# GRBLduino_Uno_Rev3-02-TH.net
KiCad netlist of a schematic drawn in EAGLE
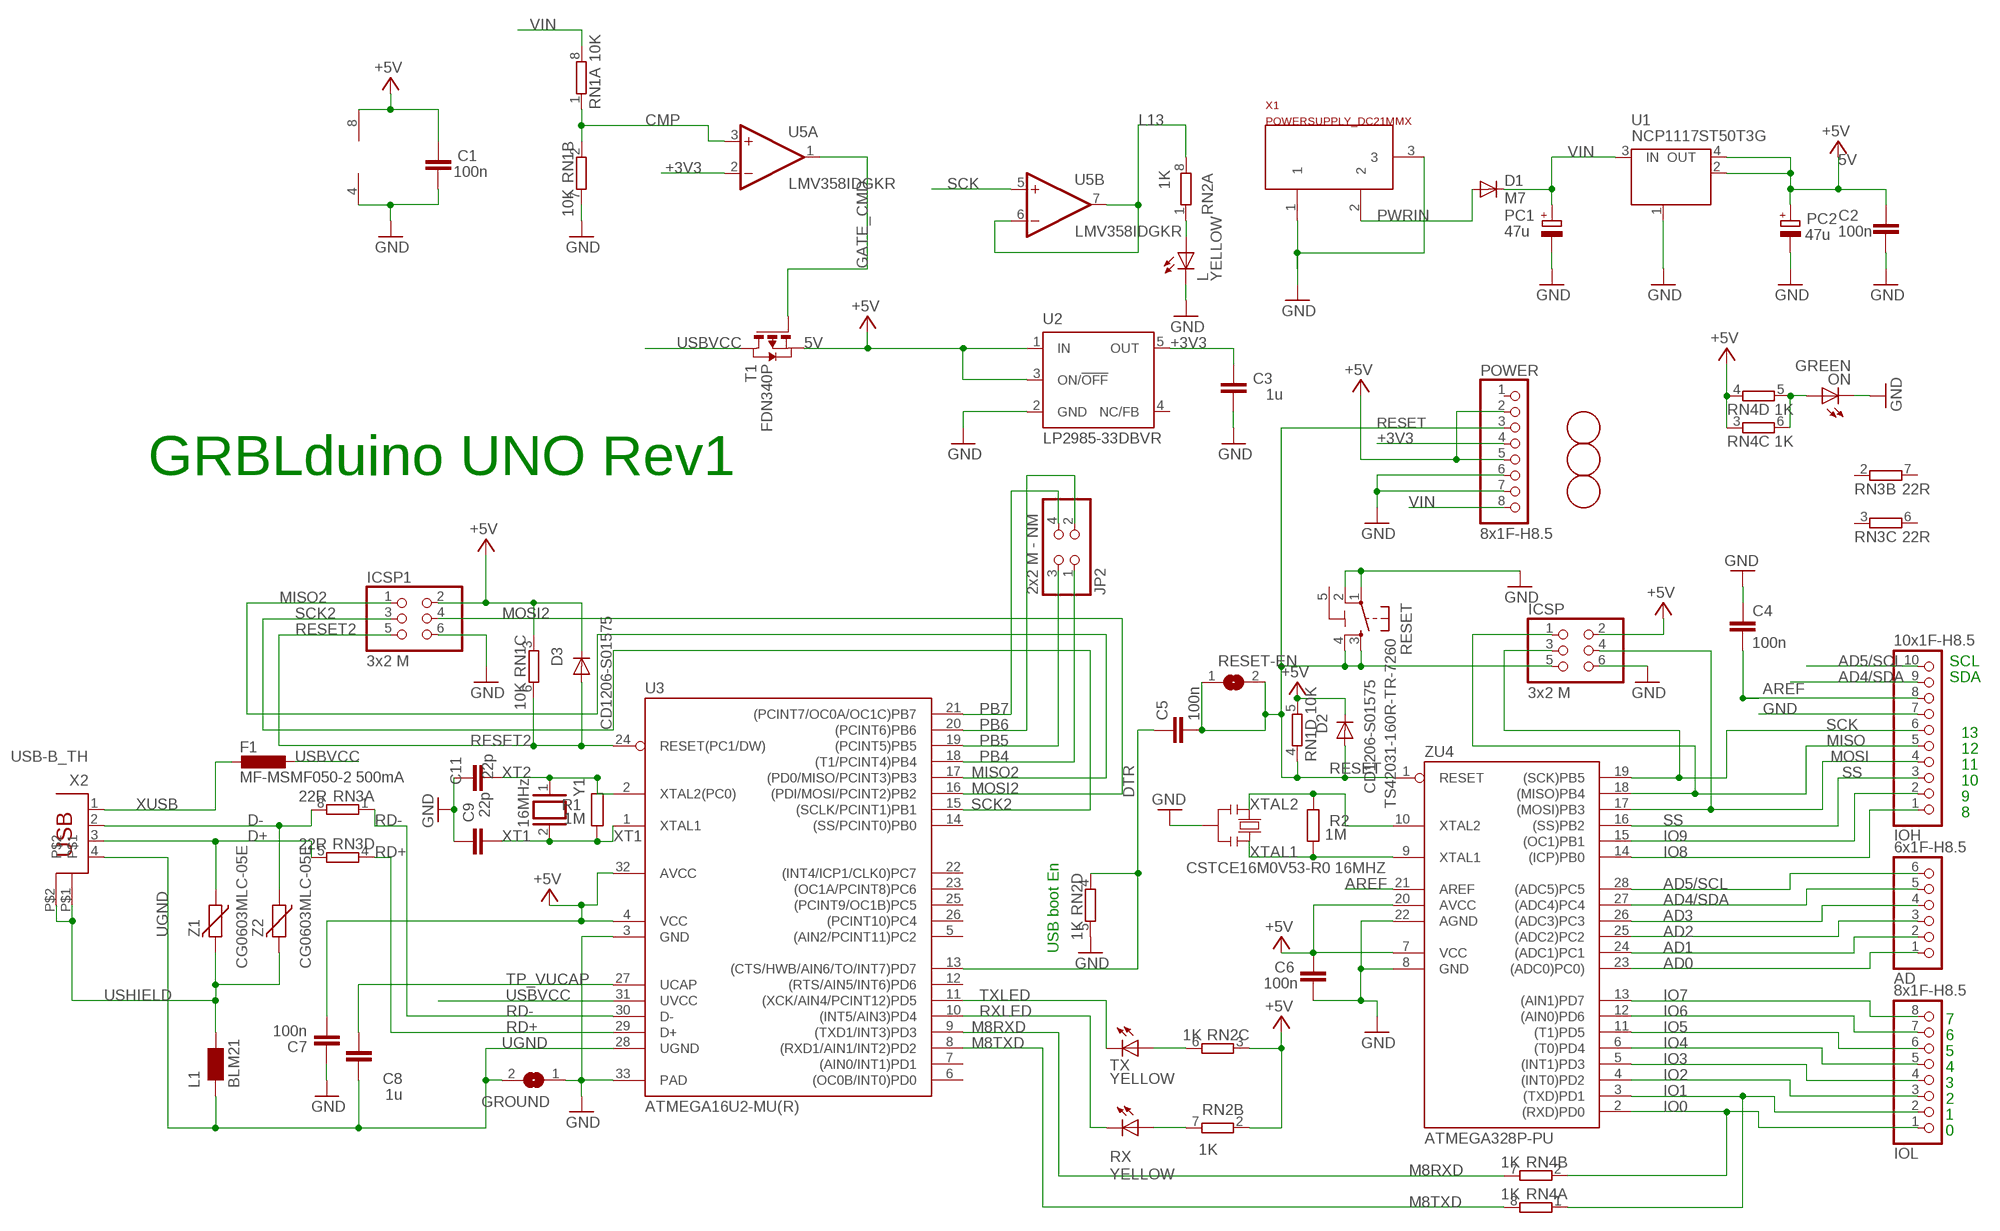
[diagram p0: schematic, sheet 1]
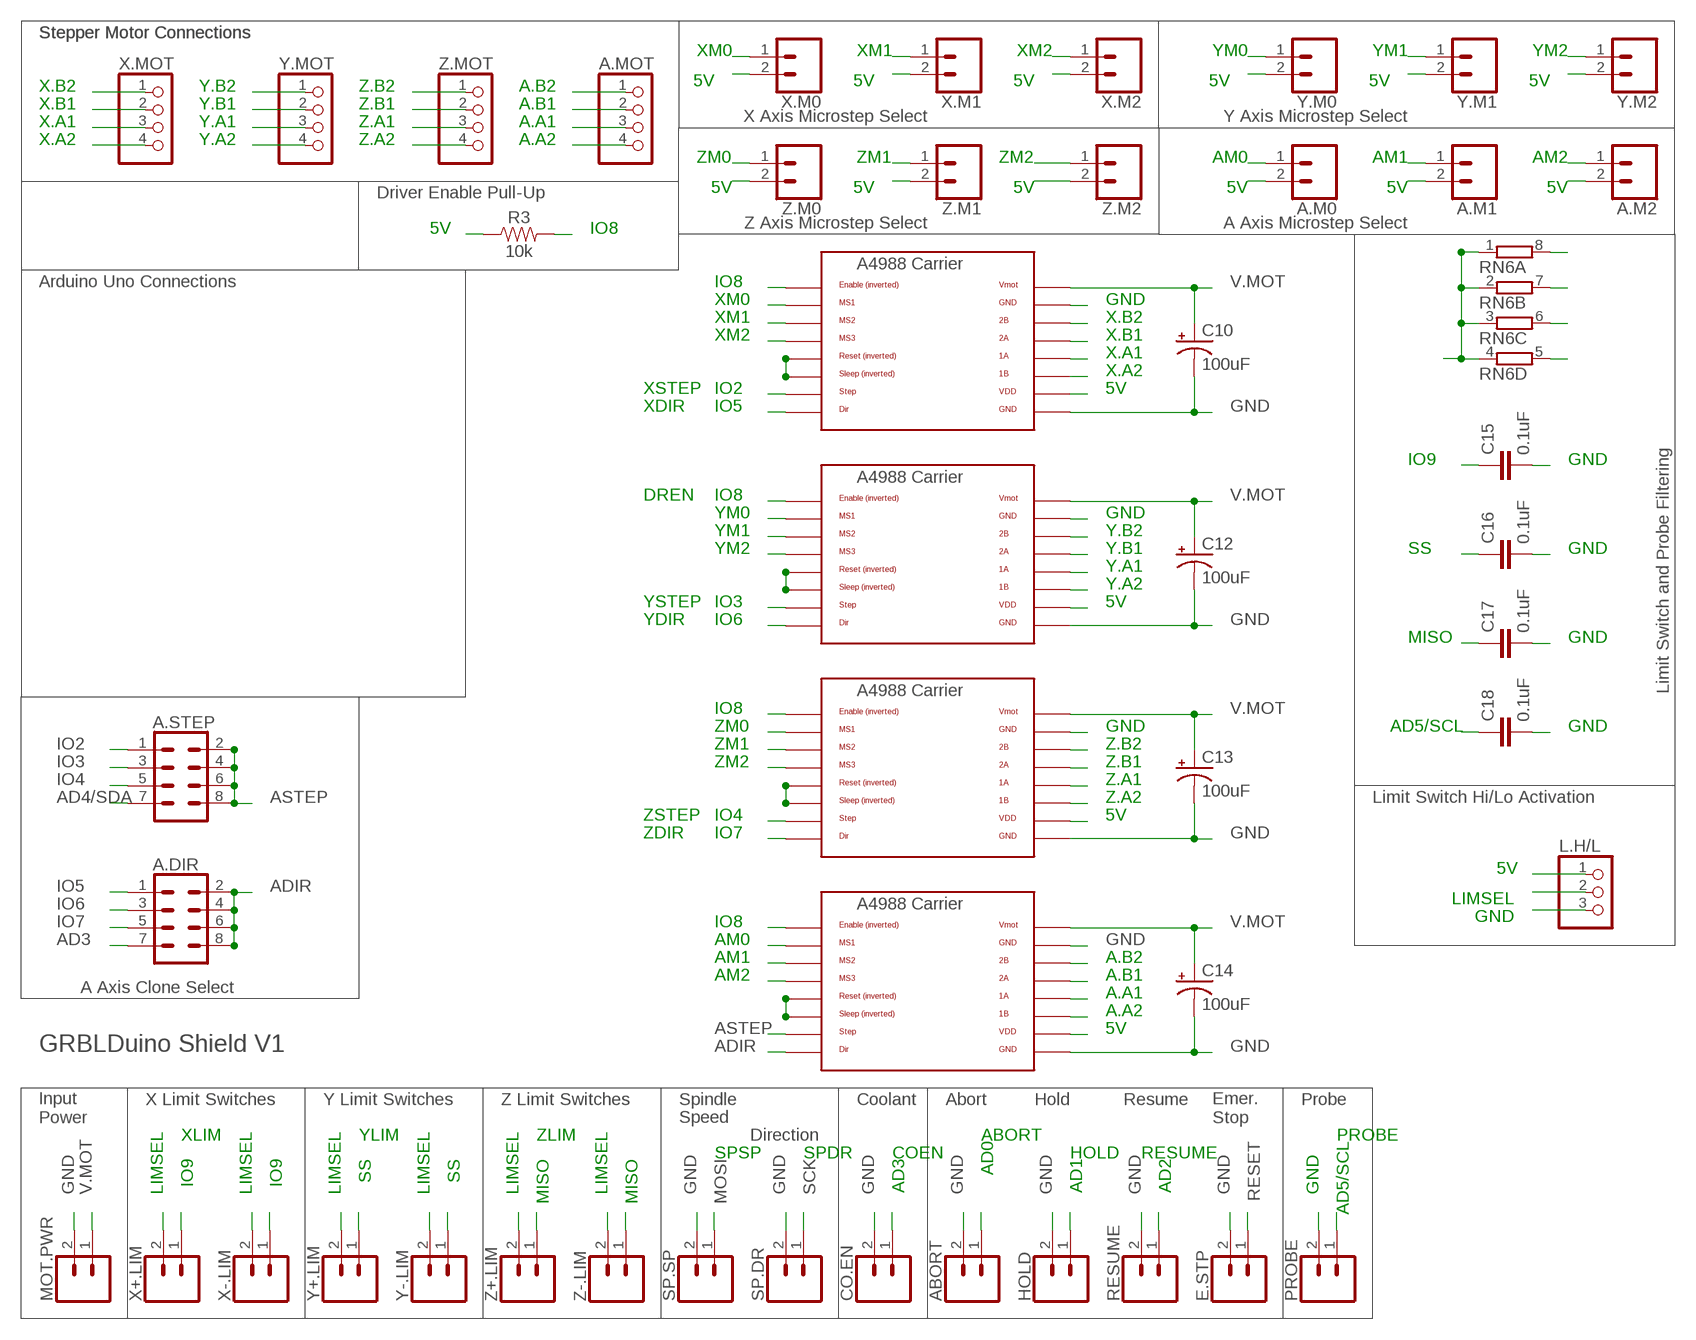
[diagram p1: schematic, sheet 2]

(export (version "E")
  (design (tool "Eeschema 10.0.6"))
  (components
    (comp (ref "AD")
      (value "6x1F-H8.5")
      (footprint "eagle-import:1X06")
      (libsource (lib "eagle-import") (part "PINHD-1X6"))
    )
    (comp (ref "C1")
      (value "100n")
      (footprint "eagle-import:C0603-ROUND")
      (libsource (lib "eagle-import") (part "C-EU0603-RND"))
    )
    (comp (ref "C2")
      (value "100n")
      (footprint "eagle-import:C0603-ROUND")
      (libsource (lib "eagle-import") (part "C-EU0603-RND"))
    )
    (comp (ref "C3")
      (value "1u")
      (footprint "eagle-import:C0603-ROUND")
      (libsource (lib "eagle-import") (part "C-EU0603-RND"))
    )
    (comp (ref "C4")
      (value "100n")
      (footprint "eagle-import:C0603-ROUND")
      (libsource (lib "eagle-import") (part "C-EU0603-RND"))
    )
    (comp (ref "C5")
      (value "100n")
      (footprint "eagle-import:C0603-ROUND")
      (libsource (lib "eagle-import") (part "C-EU0603-RND"))
    )
    (comp (ref "C6")
      (value "100n")
      (footprint "eagle-import:C0603-ROUND")
      (libsource (lib "eagle-import") (part "C-EU0603-RND"))
    )
    (comp (ref "C7")
      (value "100n")
      (footprint "eagle-import:C0603-ROUND")
      (libsource (lib "eagle-import") (part "C-EU0603-RND"))
    )
    (comp (ref "C8")
      (value "1u")
      (footprint "eagle-import:C0603-ROUND")
      (libsource (lib "eagle-import") (part "C-EU0603-RND"))
    )
    (comp (ref "C9")
      (value "22p")
      (footprint "eagle-import:C0603-ROUND")
      (libsource (lib "eagle-import") (part "C-EU0603-RND"))
    )
    (comp (ref "C11")
      (value "22p")
      (footprint "eagle-import:C0603-ROUND")
      (libsource (lib "eagle-import") (part "C-EU0603-RND"))
    )
    (comp (ref "D1")
      (value "M7")
      (footprint "eagle-import:SMB")
      (libsource (lib "eagle-import") (part "DIODE-SMB"))
    )
    (comp (ref "D2")
      (value "CD1206-S01575")
      (footprint "eagle-import:MINIMELF")
      (libsource (lib "eagle-import") (part "DIODE-MINIMELF"))
    )
    (comp (ref "D3")
      (value "CD1206-S01575")
      (footprint "eagle-import:MINIMELF")
      (libsource (lib "eagle-import") (part "DIODE-MINIMELF"))
    )
    (comp (ref "F1")
      (value "MF-MSMF050-2 500mA")
      (footprint "eagle-import:L1812")
      (libsource (lib "eagle-import") (part "L-EUL1812"))
    )
    (comp (ref "FD1")
      (value "FIDUCIALMOUNT")
      (footprint "eagle-import:FIDUCIA-MOUNT")
      (libsource (lib "eagle-import") (part "FIDUCIALMOUNT"))
    )
    (comp (ref "FD2")
      (value "FIDUCIALMOUNT")
      (footprint "eagle-import:FIDUCIA-MOUNT")
      (libsource (lib "eagle-import") (part "FIDUCIALMOUNT"))
    )
    (comp (ref "FD3")
      (value "FIDUCIALMOUNT")
      (footprint "eagle-import:FIDUCIA-MOUNT")
      (libsource (lib "eagle-import") (part "FIDUCIALMOUNT"))
    )
    (comp (ref "GROUND")
      (value "SJ")
      (footprint "eagle-import:SJ")
      (libsource (lib "eagle-import") (part "SJ"))
    )
    (comp (ref "ICSP")
      (value "3x2 M")
      (footprint "eagle-import:2X03")
      (libsource (lib "eagle-import") (part "PINHD-2X3"))
    )
    (comp (ref "ICSP1")
      (value "3x2 M")
      (footprint "eagle-import:2X03")
      (libsource (lib "eagle-import") (part "PINHD-2X3"))
    )
    (comp (ref "IOH")
      (value "10x1F-H8.5")
      (footprint "eagle-import:1X10")
      (libsource (lib "eagle-import") (part "PINHD-1X10_ARD"))
    )
    (comp (ref "IOL")
      (value "8x1F-H8.5")
      (footprint "eagle-import:1X08")
      (libsource (lib "eagle-import") (part "PINHD-1X8"))
    )
    (comp (ref "JP2")
      (value "2x2 M - NM")
      (footprint "eagle-import:2X02")
      (libsource (lib "eagle-import") (part "PINHD-2X2"))
    )
    (comp (ref "L")
      (value "YELLOW")
      (footprint "eagle-import:CHIP-LED0805")
      (libsource (lib "eagle-import") (part "LEDCHIP-LED0805"))
    )
    (comp (ref "L1")
      (value "BLM21")
      (footprint "eagle-import:0805")
      (libsource (lib "eagle-import") (part "WE-CBF_0805"))
    )
    (comp (ref "ON")
      (value "GREEN")
      (footprint "eagle-import:CHIP-LED0805")
      (libsource (lib "eagle-import") (part "LEDCHIP-LED0805"))
    )
    (comp (ref "PC1")
      (value "47u")
      (footprint "eagle-import:PANASONIC_D")
      (libsource (lib "eagle-import") (part "CPOL-EUD"))
    )
    (comp (ref "PC2")
      (value "47u")
      (footprint "eagle-import:PANASONIC_D")
      (libsource (lib "eagle-import") (part "CPOL-EUD"))
    )
    (comp (ref "POWER")
      (value "8x1F-H8.5")
      (footprint "eagle-import:1X08")
      (libsource (lib "eagle-import") (part "PINHD-1X8"))
    )
    (comp (ref "R1")
      (value "1M")
      (footprint "eagle-import:R0603-ROUND")
      (libsource (lib "eagle-import") (part "R-EU_R0603"))
    )
    (comp (ref "R2")
      (value "1M")
      (footprint "eagle-import:R0603-ROUND")
      (libsource (lib "eagle-import") (part "R-EU_R0603"))
    )
    (comp (ref "RESET")
      (value "TS42031-160R-TR-7260")
      (footprint "eagle-import:TS42")
      (libsource (lib "eagle-import") (part "TS42"))
    )
    (comp (ref "RESET-EN")
      (value "SJ")
      (footprint "eagle-import:SJ")
      (libsource (lib "eagle-import") (part "SJ"))
    )
    (comp (ref "RN1")
      (value "10K")
      (footprint "eagle-import:CAY16")
      (libsource (lib "eagle-import") (part "4R-NCAY16"))
    )
    (comp (ref "RN2")
      (value "1K")
      (footprint "eagle-import:CAY16")
      (libsource (lib "eagle-import") (part "4R-NCAY16"))
    )
    (comp (ref "RN3")
      (value "22R")
      (footprint "eagle-import:CAY16")
      (libsource (lib "eagle-import") (part "4R-NCAY16"))
    )
    (comp (ref "RN4")
      (value "1K")
      (footprint "eagle-import:CAY16")
      (libsource (lib "eagle-import") (part "4R-NCAY16"))
    )
    (comp (ref "RX")
      (value "YELLOW")
      (footprint "eagle-import:CHIP-LED0805")
      (libsource (lib "eagle-import") (part "LEDCHIP-LED0805"))
    )
    (comp (ref "T1")
      (value "FDN340P")
      (footprint "eagle-import:SOT-23")
      (libsource (lib "eagle-import") (part "PMOSSOT23"))
    )
    (comp (ref "TX")
      (value "YELLOW")
      (footprint "eagle-import:CHIP-LED0805")
      (libsource (lib "eagle-import") (part "LEDCHIP-LED0805"))
    )
    (comp (ref "U1")
      (value "NCP1117ST50T3G")
      (footprint "eagle-import:SOT223")
      (libsource (lib "eagle-import") (part "MC33269ST-3.3T3"))
    )
    (comp (ref "U2")
      (value "LP2985-33DBVR")
      (footprint "eagle-import:SOT23-DBV")
      (libsource (lib "eagle-import") (part "LP2985-XXDBVR33"))
    )
    (comp (ref "U3")
      (value "ATMEGA16U2-MU(R)")
      (footprint "eagle-import:MLF32")
      (libsource (lib "eagle-import") (part "ATMEGA16U2-MU"))
    )
    (comp (ref "U5")
      (value "LMV358IDGKR")
      (footprint "eagle-import:MSOP08")
      (libsource (lib "eagle-import") (part "LMV358?MMX"))
    )
    (comp (ref "X1")
      (value "POWERSUPPLY_DC21MMX")
      (footprint "eagle-import:POWERSUPPLY_DC-21MM")
      (libsource (lib "eagle-import") (part "POWERSUPPLY_DC21MMX"))
    )
    (comp (ref "X2")
      (value "USB-B_TH")
      (footprint "eagle-import:PN61729")
      (libsource (lib "eagle-import") (part "PN61729"))
    )
    (comp (ref "Y1")
      (value "16MHz")
      (footprint "eagle-import:QS")
      (libsource (lib "eagle-import") (part "XTAL/S"))
    )
    (comp (ref "Y2")
      (value "CSTCE16M0V53-R0 16MHZ")
      (footprint "eagle-import:RESONATOR")
      (libsource (lib "eagle-import") (part "RESONATORMU"))
    )
    (comp (ref "Z1")
      (value "CG0603MLC-05E")
      (footprint "eagle-import:CT_CN0603")
      (libsource (lib "eagle-import") (part "VARISTORCN0603"))
    )
    (comp (ref "Z2")
      (value "CG0603MLC-05E")
      (footprint "eagle-import:CT_CN0603")
      (libsource (lib "eagle-import") (part "VARISTORCN0603"))
    )
    (comp (ref "ZU4")
      (value "ATMEGA328P-PU")
      (footprint "eagle-import:DIL28-3")
      (libsource (lib "eagle-import") (part "ATMEGA328P-PU"))
    )
    (comp (ref "A.DIR")
      (value "CONN_04X2")
      (footprint "eagle-import:2X4")
      (libsource (lib "eagle-import") (part "CONN_04X2"))
    )
    (comp (ref "A.DRV")
      (value "A Driver")
      (footprint "eagle-import:A4988BREAKOUT")
      (libsource (lib "eagle-import") (part "A4988BREAKOUT"))
    )
    (comp (ref "A.M0")
      (value "CONN_02")
      (footprint "eagle-import:1X02")
      (libsource (lib "eagle-import") (part "CONN_02"))
    )
    (comp (ref "A.M1")
      (value "CONN_02")
      (footprint "eagle-import:1X02")
      (libsource (lib "eagle-import") (part "CONN_02"))
    )
    (comp (ref "A.M2")
      (value "CONN_02")
      (footprint "eagle-import:1X02")
      (libsource (lib "eagle-import") (part "CONN_02"))
    )
    (comp (ref "A.MOT")
      (value "PINHD-1X4")
      (footprint "eagle-import:1X04")
      (libsource (lib "eagle-import") (part "PINHD-1X4"))
    )
    (comp (ref "A.STEP")
      (value "CONN_04X2")
      (footprint "eagle-import:2X4")
      (libsource (lib "eagle-import") (part "CONN_04X2"))
    )
    (comp (ref "ABORT")
      (value "CONN_025MM")
      (footprint "eagle-import:SCREWTERMINAL-5MM-2")
      (libsource (lib "eagle-import") (part "CONN_025MM"))
    )
    (comp (ref "C10")
      (value "100uF")
      (footprint "eagle-import:CPOL-RADIAL-2.5MM-6.5MM")
      (libsource (lib "eagle-import") (part "100UF-POLAR-RADIAL-2.5MM-25V-20%"))
    )
    (comp (ref "C12")
      (value "100uF")
      (footprint "eagle-import:CPOL-RADIAL-2.5MM-6.5MM")
      (libsource (lib "eagle-import") (part "100UF-POLAR-RADIAL-2.5MM-25V-20%"))
    )
    (comp (ref "C13")
      (value "100uF")
      (footprint "eagle-import:CPOL-RADIAL-2.5MM-6.5MM")
      (libsource (lib "eagle-import") (part "100UF-POLAR-RADIAL-2.5MM-25V-20%"))
    )
    (comp (ref "C14")
      (value "100uF")
      (footprint "eagle-import:CPOL-RADIAL-2.5MM-6.5MM")
      (libsource (lib "eagle-import") (part "100UF-POLAR-RADIAL-2.5MM-25V-20%"))
    )
    (comp (ref "C15")
      (value "0.1uF")
      (footprint "eagle-import:0603")
      (libsource (lib "eagle-import") (part "0.1UF-0603-25V-5%"))
    )
    (comp (ref "C16")
      (value "0.1uF")
      (footprint "eagle-import:0603")
      (libsource (lib "eagle-import") (part "0.1UF-0603-25V-5%"))
    )
    (comp (ref "C17")
      (value "0.1uF")
      (footprint "eagle-import:0603")
      (libsource (lib "eagle-import") (part "0.1UF-0603-25V-5%"))
    )
    (comp (ref "C18")
      (value "0.1uF")
      (footprint "eagle-import:0603")
      (libsource (lib "eagle-import") (part "0.1UF-0603-25V-5%"))
    )
    (comp (ref "CO.EN")
      (value "CONN_025MM")
      (footprint "eagle-import:SCREWTERMINAL-5MM-2")
      (libsource (lib "eagle-import") (part "CONN_025MM"))
    )
    (comp (ref "E.STP")
      (value "CONN_025MM")
      (footprint "eagle-import:SCREWTERMINAL-5MM-2")
      (libsource (lib "eagle-import") (part "CONN_025MM"))
    )
    (comp (ref "HOLD")
      (value "CONN_025MM")
      (footprint "eagle-import:SCREWTERMINAL-5MM-2")
      (libsource (lib "eagle-import") (part "CONN_025MM"))
    )
    (comp (ref "L.H/L")
      (value "PINHD-1X3")
      (footprint "eagle-import:1X03")
      (libsource (lib "eagle-import") (part "PINHD-1X3"))
    )
    (comp (ref "MOT.PWR")
      (value "CONN_025MM")
      (footprint "eagle-import:SCREWTERMINAL-5MM-2")
      (libsource (lib "eagle-import") (part "CONN_025MM"))
    )
    (comp (ref "PROBE")
      (value "CONN_025MM")
      (footprint "eagle-import:SCREWTERMINAL-5MM-2")
      (libsource (lib "eagle-import") (part "CONN_025MM"))
    )
    (comp (ref "R3")
      (value "10k")
      (footprint "eagle-import:0603")
      (libsource (lib "eagle-import") (part "10KOHM-0603-1/10W-1%"))
    )
    (comp (ref "RESUME")
      (value "CONN_025MM")
      (footprint "eagle-import:SCREWTERMINAL-5MM-2")
      (libsource (lib "eagle-import") (part "CONN_025MM"))
    )
    (comp (ref "RN6")
      (value "4R-N0603-ARC")
      (footprint "eagle-import:0603-ARC")
      (libsource (lib "eagle-import") (part "4R-N0603-ARC"))
    )
    (comp (ref "SP.DR")
      (value "CONN_025MM")
      (footprint "eagle-import:SCREWTERMINAL-5MM-2")
      (libsource (lib "eagle-import") (part "CONN_025MM"))
    )
    (comp (ref "SP.SP")
      (value "CONN_025MM")
      (footprint "eagle-import:SCREWTERMINAL-5MM-2")
      (libsource (lib "eagle-import") (part "CONN_025MM"))
    )
    (comp (ref "X+.LIM")
      (value "CONN_025MM")
      (footprint "eagle-import:SCREWTERMINAL-5MM-2")
      (libsource (lib "eagle-import") (part "CONN_025MM"))
    )
    (comp (ref "X-.LIM")
      (value "CONN_025MM")
      (footprint "eagle-import:SCREWTERMINAL-5MM-2")
      (libsource (lib "eagle-import") (part "CONN_025MM"))
    )
    (comp (ref "X.DRV")
      (value "X Driver")
      (footprint "eagle-import:A4988BREAKOUT")
      (libsource (lib "eagle-import") (part "POLOLU_A4983CARRIER"))
    )
    (comp (ref "X.M0")
      (value "CONN_02")
      (footprint "eagle-import:1X02")
      (libsource (lib "eagle-import") (part "CONN_02"))
    )
    (comp (ref "X.M1")
      (value "CONN_02")
      (footprint "eagle-import:1X02")
      (libsource (lib "eagle-import") (part "CONN_02"))
    )
    (comp (ref "X.M2")
      (value "CONN_02")
      (footprint "eagle-import:1X02")
      (libsource (lib "eagle-import") (part "CONN_02"))
    )
    (comp (ref "X.MOT")
      (value "PINHD-1X4")
      (footprint "eagle-import:1X04")
      (libsource (lib "eagle-import") (part "PINHD-1X4"))
    )
    (comp (ref "Y+.LIM")
      (value "CONN_025MM")
      (footprint "eagle-import:SCREWTERMINAL-5MM-2")
      (libsource (lib "eagle-import") (part "CONN_025MM"))
    )
    (comp (ref "Y-.LIM")
      (value "CONN_025MM")
      (footprint "eagle-import:SCREWTERMINAL-5MM-2")
      (libsource (lib "eagle-import") (part "CONN_025MM"))
    )
    (comp (ref "Y.DRV")
      (value "Y Driver")
      (footprint "eagle-import:A4988BREAKOUT")
      (libsource (lib "eagle-import") (part "POLOLU_A4983CARRIER"))
    )
    (comp (ref "Y.M0")
      (value "CONN_02")
      (footprint "eagle-import:1X02")
      (libsource (lib "eagle-import") (part "CONN_02"))
    )
    (comp (ref "Y.M1")
      (value "CONN_02")
      (footprint "eagle-import:1X02")
      (libsource (lib "eagle-import") (part "CONN_02"))
    )
    (comp (ref "Y.M2")
      (value "CONN_02")
      (footprint "eagle-import:1X02")
      (libsource (lib "eagle-import") (part "CONN_02"))
    )
    (comp (ref "Y.MOT")
      (value "PINHD-1X4")
      (footprint "eagle-import:1X04")
      (libsource (lib "eagle-import") (part "PINHD-1X4"))
    )
    (comp (ref "Z+.LIM")
      (value "CONN_025MM")
      (footprint "eagle-import:SCREWTERMINAL-5MM-2")
      (libsource (lib "eagle-import") (part "CONN_025MM"))
    )
    (comp (ref "Z-.LIM")
      (value "CONN_025MM")
      (footprint "eagle-import:SCREWTERMINAL-5MM-2")
      (libsource (lib "eagle-import") (part "CONN_025MM"))
    )
    (comp (ref "Z.DRV")
      (value "Z Driver")
      (footprint "eagle-import:A4988BREAKOUT")
      (libsource (lib "eagle-import") (part "POLOLU_A4983CARRIER"))
    )
    (comp (ref "Z.M0")
      (value "CONN_02")
      (footprint "eagle-import:1X02")
      (libsource (lib "eagle-import") (part "CONN_02"))
    )
    (comp (ref "Z.M1")
      (value "CONN_02")
      (footprint "eagle-import:1X02")
      (libsource (lib "eagle-import") (part "CONN_02"))
    )
    (comp (ref "Z.M2")
      (value "CONN_02")
      (footprint "eagle-import:1X02")
      (libsource (lib "eagle-import") (part "CONN_02"))
    )
    (comp (ref "Z.MOT")
      (value "PINHD-1X4")
      (footprint "eagle-import:1X04")
      (libsource (lib "eagle-import") (part "PINHD-1X4"))
    )
  )
  (nets
    (net (code "1") (name "+3V3") (class "Default")
      (node (ref "C3") (pin "2") (pinfunction "2_2") (pintype "passive"))
      (node (ref "POWER") (pin "4") (pinfunction "4_4") (pintype "passive"))
      (node (ref "U2") (pin "5") (pinfunction "OUT_5") (pintype "passive"))
      (node (ref "U5") (pin "2") (pinfunction "-IN_2") (pintype "input"))
    )
    (net (code "2") (name "5-GND") (class "Default")
      (node (ref "RESET") (pin "5") (pinfunction "5-GND_5") (pintype "power_in"))
    )
    (net (code "3") (name "5V") (class "Default")
      (node (ref "A.DRV") (pin "VDD") (pinfunction "VDD_VDD") (pintype "power_in"))
      (node (ref "A.M0") (pin "2") (pinfunction "2_2") (pintype "passive"))
      (node (ref "A.M1") (pin "2") (pinfunction "2_2") (pintype "passive"))
      (node (ref "A.M2") (pin "2") (pinfunction "2_2") (pintype "passive"))
      (node (ref "C1") (pin "2") (pinfunction "2_2") (pintype "passive"))
      (node (ref "C2") (pin "2") (pinfunction "2_2") (pintype "passive"))
      (node (ref "C6") (pin "2") (pinfunction "2_2") (pintype "passive"))
      (node (ref "C7") (pin "1") (pinfunction "1_1") (pintype "passive"))
      (node (ref "D2") (pin "C") (pinfunction "C_C") (pintype "passive"))
      (node (ref "D3") (pin "C") (pinfunction "C_C") (pintype "passive"))
      (node (ref "ICSP") (pin "2") (pinfunction "2_2") (pintype "passive"))
      (node (ref "ICSP1") (pin "2") (pinfunction "2_2") (pintype "passive"))
      (node (ref "L.H/L") (pin "1") (pinfunction "1_1") (pintype "passive"))
      (node (ref "PC2") (pin "+") (pinfunction "+_+") (pintype "passive"))
      (node (ref "POWER") (pin "2") (pinfunction "2_2") (pintype "passive"))
      (node (ref "POWER") (pin "5") (pinfunction "5_5") (pintype "passive"))
      (node (ref "R3") (pin "1") (pinfunction "1_1") (pintype "passive"))
      (node (ref "RN1") (pin "3") (pinfunction "1_3") (pintype "passive"))
      (node (ref "RN1") (pin "5") (pinfunction "2_5") (pintype "passive"))
      (node (ref "RN2") (pin "2") (pinfunction "1_2") (pintype "passive"))
      (node (ref "RN2") (pin "3") (pinfunction "1_3") (pintype "passive"))
      (node (ref "RN4") (pin "3") (pinfunction "1_3") (pintype "passive"))
      (node (ref "RN4") (pin "4") (pinfunction "1_4") (pintype "passive"))
      (node (ref "RN6") (pin "1") (pinfunction "1_1") (pintype "passive"))
      (node (ref "RN6") (pin "2") (pinfunction "1_2") (pintype "passive"))
      (node (ref "RN6") (pin "3") (pinfunction "1_3") (pintype "passive"))
      (node (ref "RN6") (pin "4") (pinfunction "1_4") (pintype "passive"))
      (node (ref "T1") (pin "2") (pinfunction "S_2") (pintype "passive"))
      (node (ref "U1") (pin "2") (pinfunction "OUT_2") (pintype "passive"))
      (node (ref "U1") (pin "4") (pinfunction "OUT_4") (pintype "passive"))
      (node (ref "U2") (pin "1") (pinfunction "IN_1") (pintype "input"))
      (node (ref "U2") (pin "3") (pinfunction "ON/~{OFF}_3") (pintype "input"))
      (node (ref "U3") (pin "32") (pinfunction "AVCC_32") (pintype "power_in"))
      (node (ref "U3") (pin "4") (pinfunction "VCC_4") (pintype "power_in"))
      (node (ref "U5") (pin "8") (pinfunction "V+_8") (pintype "power_in"))
      (node (ref "X.DRV") (pin "VDD") (pinfunction "VDD_VDD") (pintype "power_in"))
      (node (ref "X.M0") (pin "2") (pinfunction "2_2") (pintype "passive"))
      (node (ref "X.M1") (pin "2") (pinfunction "2_2") (pintype "passive"))
      (node (ref "X.M2") (pin "2") (pinfunction "2_2") (pintype "passive"))
      (node (ref "Y.DRV") (pin "VDD") (pinfunction "VDD_VDD") (pintype "power_in"))
      (node (ref "Y.M0") (pin "2") (pinfunction "2_2") (pintype "passive"))
      (node (ref "Y.M1") (pin "2") (pinfunction "2_2") (pintype "passive"))
      (node (ref "Y.M2") (pin "2") (pinfunction "2_2") (pintype "passive"))
      (node (ref "Z.DRV") (pin "VDD") (pinfunction "VDD_VDD") (pintype "power_in"))
      (node (ref "Z.M0") (pin "2") (pinfunction "2_2") (pintype "passive"))
      (node (ref "Z.M1") (pin "2") (pinfunction "2_2") (pintype "passive"))
      (node (ref "Z.M2") (pin "2") (pinfunction "2_2") (pintype "passive"))
      (node (ref "ZU4") (pin "20") (pinfunction "AVCC_20") (pintype "power_in"))
      (node (ref "ZU4") (pin "7") (pinfunction "VCC_7") (pintype "power_in"))
    )
    (net (code "4") (name "A.A1") (class "Default")
      (node (ref "A.DRV") (pin "1A") (pinfunction "1A_1A") (pintype "output"))
      (node (ref "A.MOT") (pin "3") (pinfunction "3_3") (pintype "passive"))
    )
    (net (code "5") (name "A.A2") (class "Default")
      (node (ref "A.DRV") (pin "1B") (pinfunction "1B_1B") (pintype "output"))
      (node (ref "A.MOT") (pin "4") (pinfunction "4_4") (pintype "passive"))
    )
    (net (code "6") (name "A.B1") (class "Default")
      (node (ref "A.DRV") (pin "2A") (pinfunction "2A_2A") (pintype "output"))
      (node (ref "A.MOT") (pin "2") (pinfunction "2_2") (pintype "passive"))
    )
    (net (code "7") (name "A.B2") (class "Default")
      (node (ref "A.DRV") (pin "2B") (pinfunction "2B_2B") (pintype "output"))
      (node (ref "A.MOT") (pin "1") (pinfunction "1_1") (pintype "passive"))
    )
    (net (code "8") (name "AD0") (class "Default")
      (node (ref "ABORT") (pin "1") (pinfunction "1_1") (pintype "passive"))
      (node (ref "AD") (pin "1") (pinfunction "1_1") (pintype "passive"))
      (node (ref "ZU4") (pin "23") (pinfunction "(ADC0)PC0)_23") (pintype "bidirectional"))
    )
    (net (code "9") (name "AD1") (class "Default")
      (node (ref "AD") (pin "2") (pinfunction "2_2") (pintype "passive"))
      (node (ref "HOLD") (pin "1") (pinfunction "1_1") (pintype "passive"))
      (node (ref "ZU4") (pin "24") (pinfunction "(ADC1)PC1_24") (pintype "bidirectional"))
    )
    (net (code "10") (name "AD2") (class "Default")
      (node (ref "AD") (pin "3") (pinfunction "3_3") (pintype "passive"))
      (node (ref "RESUME") (pin "1") (pinfunction "1_1") (pintype "passive"))
      (node (ref "ZU4") (pin "25") (pinfunction "(ADC2)PC2_25") (pintype "bidirectional"))
    )
    (net (code "11") (name "AD3") (class "Default")
      (node (ref "A.DIR") (pin "7") (pinfunction "7_7") (pintype "passive"))
      (node (ref "AD") (pin "4") (pinfunction "4_4") (pintype "passive"))
      (node (ref "CO.EN") (pin "1") (pinfunction "1_1") (pintype "passive"))
      (node (ref "ZU4") (pin "26") (pinfunction "(ADC3)PC3_26") (pintype "bidirectional"))
    )
    (net (code "12") (name "AD4{slash}SDA") (class "Default")
      (node (ref "A.STEP") (pin "7") (pinfunction "7_7") (pintype "passive"))
      (node (ref "AD") (pin "5") (pinfunction "5_5") (pintype "passive"))
      (node (ref "IOH") (pin "9") (pinfunction "9_9") (pintype "passive"))
      (node (ref "ZU4") (pin "27") (pinfunction "(ADC4)PC4_27") (pintype "bidirectional"))
    )
    (net (code "13") (name "AD5{slash}SCL") (class "Default")
      (node (ref "AD") (pin "6") (pinfunction "6_6") (pintype "passive"))
      (node (ref "C18") (pin "1") (pinfunction "1_1") (pintype "passive"))
      (node (ref "IOH") (pin "10") (pinfunction "10_10") (pintype "passive"))
      (node (ref "PROBE") (pin "1") (pinfunction "1_1") (pintype "passive"))
      (node (ref "RN6") (pin "5") (pinfunction "2_5") (pintype "passive"))
      (node (ref "ZU4") (pin "28") (pinfunction "(ADC5)PC5_28") (pintype "bidirectional"))
    )
    (net (code "14") (name "ADIR") (class "Default")
      (node (ref "A.DIR") (pin "2") (pinfunction "2_2") (pintype "passive"))
      (node (ref "A.DIR") (pin "4") (pinfunction "4_4") (pintype "passive"))
      (node (ref "A.DIR") (pin "6") (pinfunction "6_6") (pintype "passive"))
      (node (ref "A.DIR") (pin "8") (pinfunction "8_8") (pintype "passive"))
      (node (ref "A.DRV") (pin "DIR") (pinfunction "DIR_DIR") (pintype "input"))
    )
    (net (code "15") (name "AM0") (class "Default")
      (node (ref "A.DRV") (pin "MS1") (pinfunction "MS1_MS1") (pintype "input"))
      (node (ref "A.M0") (pin "1") (pinfunction "1_1") (pintype "passive"))
    )
    (net (code "16") (name "AM1") (class "Default")
      (node (ref "A.DRV") (pin "MS2") (pinfunction "MS2_MS2") (pintype "input"))
      (node (ref "A.M1") (pin "1") (pinfunction "1_1") (pintype "passive"))
    )
    (net (code "17") (name "AM2") (class "Default")
      (node (ref "A.DRV") (pin "MS3") (pinfunction "MS3_MS3") (pintype "input"))
      (node (ref "A.M2") (pin "1") (pinfunction "1_1") (pintype "passive"))
    )
    (net (code "18") (name "AREF") (class "Default")
      (node (ref "C4") (pin "2") (pinfunction "2_2") (pintype "passive"))
      (node (ref "IOH") (pin "8") (pinfunction "8_8") (pintype "passive"))
      (node (ref "ZU4") (pin "21") (pinfunction "AREF_21") (pintype "passive"))
    )
    (net (code "19") (name "ASTEP") (class "Default")
      (node (ref "A.DRV") (pin "STEP") (pinfunction "STEP_STEP") (pintype "input"))
      (node (ref "A.STEP") (pin "2") (pinfunction "2_2") (pintype "passive"))
      (node (ref "A.STEP") (pin "4") (pinfunction "4_4") (pintype "passive"))
      (node (ref "A.STEP") (pin "6") (pinfunction "6_6") (pintype "passive"))
      (node (ref "A.STEP") (pin "8") (pinfunction "8_8") (pintype "passive"))
    )
    (net (code "20") (name "CMP") (class "Default")
      (node (ref "RN1") (pin "1") (pinfunction "1_1") (pintype "passive"))
      (node (ref "RN1") (pin "2") (pinfunction "1_2") (pintype "passive"))
      (node (ref "U5") (pin "3") (pinfunction "+IN_3") (pintype "input"))
    )
    (net (code "21") (name "D+") (class "Default")
      (node (ref "RN3") (pin "5") (pinfunction "2_5") (pintype "passive"))
      (node (ref "X2") (pin "3") (pinfunction "3_3") (pintype "bidirectional"))
      (node (ref "Z1") (pin "1") (pinfunction "1_1") (pintype "passive"))
    )
    (net (code "22") (name "D-") (class "Default")
      (node (ref "RN3") (pin "8") (pinfunction "2_8") (pintype "passive"))
      (node (ref "X2") (pin "2") (pinfunction "2_2") (pintype "bidirectional"))
      (node (ref "Z2") (pin "1") (pinfunction "1_1") (pintype "passive"))
    )
    (net (code "23") (name "DTR") (class "Default")
      (node (ref "C5") (pin "1") (pinfunction "1_1") (pintype "passive"))
      (node (ref "RN2") (pin "4") (pinfunction "1_4") (pintype "passive"))
      (node (ref "U3") (pin "13") (pinfunction "(CTS/HWB/AIN6/TO/INT7)PD7_13") (pintype "bidirectional"))
    )
    (net (code "24") (name "GATE_CMD") (class "Default")
      (node (ref "T1") (pin "3") (pinfunction "G_3") (pintype "passive"))
      (node (ref "U5") (pin "1") (pinfunction "OUT_1") (pintype "output"))
    )
    (net (code "25") (name "GND") (class "Default")
      (node (ref "A.DRV") (pin "GND") (pinfunction "GND_GND") (pintype "power_in"))
      (node (ref "A.DRV") (pin "GND@0") (pinfunction "GND_GND@0") (pintype "power_in"))
      (node (ref "ABORT") (pin "2") (pinfunction "2_2") (pintype "passive"))
      (node (ref "C1") (pin "1") (pinfunction "1_1") (pintype "passive"))
      (node (ref "C10") (pin "2") (pinfunction "-_2") (pintype "passive"))
      (node (ref "C11") (pin "2") (pinfunction "2_2") (pintype "passive"))
      (node (ref "C12") (pin "2") (pinfunction "-_2") (pintype "passive"))
      (node (ref "C13") (pin "2") (pinfunction "-_2") (pintype "passive"))
      (node (ref "C14") (pin "2") (pinfunction "-_2") (pintype "passive"))
      (node (ref "C15") (pin "2") (pinfunction "2_2") (pintype "passive"))
      (node (ref "C16") (pin "2") (pinfunction "2_2") (pintype "passive"))
      (node (ref "C17") (pin "2") (pinfunction "2_2") (pintype "passive"))
      (node (ref "C18") (pin "2") (pinfunction "2_2") (pintype "passive"))
      (node (ref "C2") (pin "1") (pinfunction "1_1") (pintype "passive"))
      (node (ref "C3") (pin "1") (pinfunction "1_1") (pintype "passive"))
      (node (ref "C4") (pin "1") (pinfunction "1_1") (pintype "passive"))
      (node (ref "C6") (pin "1") (pinfunction "1_1") (pintype "passive"))
      (node (ref "C7") (pin "2") (pinfunction "2_2") (pintype "passive"))
      (node (ref "C9") (pin "2") (pinfunction "2_2") (pintype "passive"))
      (node (ref "CO.EN") (pin "2") (pinfunction "2_2") (pintype "passive"))
      (node (ref "E.STP") (pin "2") (pinfunction "2_2") (pintype "passive"))
      (node (ref "GROUND") (pin "1") (pinfunction "1_1") (pintype "passive"))
      (node (ref "HOLD") (pin "2") (pinfunction "2_2") (pintype "passive"))
      (node (ref "ICSP") (pin "6") (pinfunction "6_6") (pintype "passive"))
      (node (ref "ICSP1") (pin "6") (pinfunction "6_6") (pintype "passive"))
      (node (ref "IOH") (pin "7") (pinfunction "7_7") (pintype "passive"))
      (node (ref "L") (pin "C") (pinfunction "C_C") (pintype "passive"))
      (node (ref "L.H/L") (pin "3") (pinfunction "3_3") (pintype "passive"))
      (node (ref "MOT.PWR") (pin "2") (pinfunction "2_2") (pintype "passive"))
      (node (ref "ON") (pin "C") (pinfunction "C_C") (pintype "passive"))
      (node (ref "PC1") (pin "-") (pinfunction "-_-") (pintype "passive"))
      (node (ref "PC2") (pin "-") (pinfunction "-_-") (pintype "passive"))
      (node (ref "POWER") (pin "6") (pinfunction "6_6") (pintype "passive"))
      (node (ref "POWER") (pin "7") (pinfunction "7_7") (pintype "passive"))
      (node (ref "PROBE") (pin "2") (pinfunction "2_2") (pintype "passive"))
      (node (ref "RESET") (pin "1") (pinfunction "1_1") (pintype "passive"))
      (node (ref "RESET") (pin "2") (pinfunction "2_2") (pintype "passive"))
      (node (ref "RESUME") (pin "2") (pinfunction "2_2") (pintype "passive"))
      (node (ref "RN1") (pin "7") (pinfunction "2_7") (pintype "passive"))
      (node (ref "RN2") (pin "5") (pinfunction "2_5") (pintype "passive"))
      (node (ref "SP.DR") (pin "2") (pinfunction "2_2") (pintype "passive"))
      (node (ref "SP.SP") (pin "2") (pinfunction "2_2") (pintype "passive"))
      (node (ref "U1") (pin "1") (pinfunction "GND/ADJ_1") (pintype "input"))
      (node (ref "U2") (pin "2") (pinfunction "GND_2") (pintype "power_in"))
      (node (ref "U3") (pin "3") (pinfunction "GND_3") (pintype "power_in"))
      (node (ref "U3") (pin "33") (pinfunction "PAD_33") (pintype "power_in"))
      (node (ref "U5") (pin "4") (pinfunction "V-_4") (pintype "power_in"))
      (node (ref "X.DRV") (pin "GND") (pinfunction "GND_GND") (pintype "power_in"))
      (node (ref "X.DRV") (pin "GND@0") (pinfunction "GND_GND@0") (pintype "power_in"))
      (node (ref "X1") (pin "1") (pinfunction "1_1") (pintype "power_in"))
      (node (ref "X1") (pin "3") (pinfunction "3_3") (pintype "power_in"))
      (node (ref "Y.DRV") (pin "GND") (pinfunction "GND_GND") (pintype "power_in"))
      (node (ref "Y.DRV") (pin "GND@0") (pinfunction "GND_GND@0") (pintype "power_in"))
      (node (ref "Y2") (pin "2") (pinfunction "2_2") (pintype "passive"))
      (node (ref "Z.DRV") (pin "GND") (pinfunction "GND_GND") (pintype "power_in"))
      (node (ref "Z.DRV") (pin "GND@0") (pinfunction "GND_GND@0") (pintype "power_in"))
      (node (ref "ZU4") (pin "22") (pinfunction "AGND_22") (pintype "power_in"))
      (node (ref "ZU4") (pin "8") (pinfunction "GND_8") (pintype "power_in"))
    )
    (net (code "26") (name "IO0") (class "Default")
      (node (ref "IOL") (pin "1") (pinfunction "1_1") (pintype "passive"))
      (node (ref "RN4") (pin "2") (pinfunction "1_2") (pintype "passive"))
      (node (ref "ZU4") (pin "2") (pinfunction "(RXD)PD0_2") (pintype "bidirectional"))
    )
    (net (code "27") (name "IO1") (class "Default")
      (node (ref "IOL") (pin "2") (pinfunction "2_2") (pintype "passive"))
      (node (ref "RN4") (pin "1") (pinfunction "1_1") (pintype "passive"))
      (node (ref "ZU4") (pin "3") (pinfunction "(TXD)PD1_3") (pintype "bidirectional"))
    )
    (net (code "28") (name "IO2") (class "Default")
      (node (ref "A.STEP") (pin "1") (pinfunction "1_1") (pintype "passive"))
      (node (ref "IOL") (pin "3") (pinfunction "3_3") (pintype "passive"))
      (node (ref "X.DRV") (pin "STEP") (pinfunction "STEP_STEP") (pintype "input"))
      (node (ref "ZU4") (pin "4") (pinfunction "(INT0)PD2_4") (pintype "bidirectional"))
    )
    (net (code "29") (name "IO3") (class "Default")
      (node (ref "A.STEP") (pin "3") (pinfunction "3_3") (pintype "passive"))
      (node (ref "IOL") (pin "4") (pinfunction "4_4") (pintype "passive"))
      (node (ref "Y.DRV") (pin "STEP") (pinfunction "STEP_STEP") (pintype "input"))
      (node (ref "ZU4") (pin "5") (pinfunction "(INT1)PD3_5") (pintype "bidirectional"))
    )
    (net (code "30") (name "IO4") (class "Default")
      (node (ref "A.STEP") (pin "5") (pinfunction "5_5") (pintype "passive"))
      (node (ref "IOL") (pin "5") (pinfunction "5_5") (pintype "passive"))
      (node (ref "Z.DRV") (pin "STEP") (pinfunction "STEP_STEP") (pintype "input"))
      (node (ref "ZU4") (pin "6") (pinfunction "(T0)PD4_6") (pintype "bidirectional"))
    )
    (net (code "31") (name "IO5") (class "Default")
      (node (ref "A.DIR") (pin "1") (pinfunction "1_1") (pintype "passive"))
      (node (ref "IOL") (pin "6") (pinfunction "6_6") (pintype "passive"))
      (node (ref "X.DRV") (pin "DIR") (pinfunction "DIR_DIR") (pintype "input"))
      (node (ref "ZU4") (pin "11") (pinfunction "(T1)PD5_11") (pintype "bidirectional"))
    )
    (net (code "32") (name "IO6") (class "Default")
      (node (ref "A.DIR") (pin "3") (pinfunction "3_3") (pintype "passive"))
      (node (ref "IOL") (pin "7") (pinfunction "7_7") (pintype "passive"))
      (node (ref "Y.DRV") (pin "DIR") (pinfunction "DIR_DIR") (pintype "input"))
      (node (ref "ZU4") (pin "12") (pinfunction "(AIN0)PD6_12") (pintype "bidirectional"))
    )
    (net (code "33") (name "IO7") (class "Default")
      (node (ref "A.DIR") (pin "5") (pinfunction "5_5") (pintype "passive"))
      (node (ref "IOL") (pin "8") (pinfunction "8_8") (pintype "passive"))
      (node (ref "Z.DRV") (pin "DIR") (pinfunction "DIR_DIR") (pintype "input"))
      (node (ref "ZU4") (pin "13") (pinfunction "(AIN1)PD7_13") (pintype "bidirectional"))
    )
    (net (code "34") (name "IO8") (class "Default")
      (node (ref "A.DRV") (pin "EN") (pinfunction "EN_EN") (pintype "input"))
      (node (ref "IOH") (pin "1") (pinfunction "1_1") (pintype "passive"))
      (node (ref "R3") (pin "2") (pinfunction "2_2") (pintype "passive"))
      (node (ref "X.DRV") (pin "EN") (pinfunction "EN_EN") (pintype "input"))
      (node (ref "Y.DRV") (pin "EN") (pinfunction "EN_EN") (pintype "input"))
      (node (ref "Z.DRV") (pin "EN") (pinfunction "EN_EN") (pintype "input"))
      (node (ref "ZU4") (pin "14") (pinfunction "(ICP)PB0_14") (pintype "bidirectional"))
    )
    (net (code "35") (name "IO9") (class "Default")
      (node (ref "C15") (pin "1") (pinfunction "1_1") (pintype "passive"))
      (node (ref "IOH") (pin "2") (pinfunction "2_2") (pintype "passive"))
      (node (ref "RN6") (pin "8") (pinfunction "2_8") (pintype "passive"))
      (node (ref "X+.LIM") (pin "1") (pinfunction "1_1") (pintype "passive"))
      (node (ref "X-.LIM") (pin "1") (pinfunction "1_1") (pintype "passive"))
      (node (ref "ZU4") (pin "15") (pinfunction "(OC1)PB1_15") (pintype "bidirectional"))
    )
    (net (code "36") (name "L13") (class "Default")
      (node (ref "RN2") (pin "8") (pinfunction "2_8") (pintype "passive"))
      (node (ref "U5") (pin "6") (pinfunction "-IN_6") (pintype "input"))
      (node (ref "U5") (pin "7") (pinfunction "OUT_7") (pintype "output"))
    )
    (net (code "37") (name "LIMSEL") (class "Default")
      (node (ref "L.H/L") (pin "2") (pinfunction "2_2") (pintype "passive"))
      (node (ref "X+.LIM") (pin "2") (pinfunction "2_2") (pintype "passive"))
      (node (ref "X-.LIM") (pin "2") (pinfunction "2_2") (pintype "passive"))
      (node (ref "Y+.LIM") (pin "2") (pinfunction "2_2") (pintype "passive"))
      (node (ref "Y-.LIM") (pin "2") (pinfunction "2_2") (pintype "passive"))
      (node (ref "Z+.LIM") (pin "2") (pinfunction "2_2") (pintype "passive"))
      (node (ref "Z-.LIM") (pin "2") (pinfunction "2_2") (pintype "passive"))
    )
    (net (code "38") (name "M8RXD") (class "Default")
      (node (ref "RN4") (pin "7") (pinfunction "2_7") (pintype "passive"))
      (node (ref "U3") (pin "9") (pinfunction "(TXD1/INT3)PD3_9") (pintype "bidirectional"))
    )
    (net (code "39") (name "M8TXD") (class "Default")
      (node (ref "RN4") (pin "8") (pinfunction "2_8") (pintype "passive"))
      (node (ref "U3") (pin "8") (pinfunction "(RXD1/AIN1/INT2)PD2_8") (pintype "bidirectional"))
    )
    (net (code "40") (name "MISO") (class "Default")
      (node (ref "C17") (pin "1") (pinfunction "1_1") (pintype "passive"))
      (node (ref "ICSP") (pin "1") (pinfunction "1_1") (pintype "passive"))
      (node (ref "IOH") (pin "5") (pinfunction "5_5") (pintype "passive"))
      (node (ref "RN6") (pin "6") (pinfunction "2_6") (pintype "passive"))
      (node (ref "Z+.LIM") (pin "1") (pinfunction "1_1") (pintype "passive"))
      (node (ref "Z-.LIM") (pin "1") (pinfunction "1_1") (pintype "passive"))
      (node (ref "ZU4") (pin "18") (pinfunction "(MISO)PB4_18") (pintype "bidirectional"))
    )
    (net (code "41") (name "MISO2") (class "Default")
      (node (ref "ICSP1") (pin "1") (pinfunction "1_1") (pintype "passive"))
      (node (ref "U3") (pin "17") (pinfunction "(PD0/MISO/PCINT3)PB3_17") (pintype "bidirectional"))
    )
    (net (code "42") (name "MOSI") (class "Default")
      (node (ref "ICSP") (pin "4") (pinfunction "4_4") (pintype "passive"))
      (node (ref "IOH") (pin "4") (pinfunction "4_4") (pintype "passive"))
      (node (ref "SP.SP") (pin "1") (pinfunction "1_1") (pintype "passive"))
      (node (ref "ZU4") (pin "17") (pinfunction "(MOSI)PB3_17") (pintype "bidirectional"))
    )
    (net (code "43") (name "MOSI2") (class "Default")
      (node (ref "ICSP1") (pin "4") (pinfunction "4_4") (pintype "passive"))
      (node (ref "U3") (pin "16") (pinfunction "(PDI/MOSI/PCINT2)PB2_16") (pintype "bidirectional"))
    )
    (net (code "44") (name "Net-(A.DRV-SLEEP)") (class "Default")
      (node (ref "A.DRV") (pin "RST") (pinfunction "RST_RST") (pintype "input"))
      (node (ref "A.DRV") (pin "SLP") (pinfunction "SLEEP_SLP") (pintype "input"))
    )
    (net (code "45") (name "Net-(L-PadA)") (class "Default")
      (node (ref "L") (pin "A") (pinfunction "A_A") (pintype "passive"))
      (node (ref "RN2") (pin "1") (pinfunction "1_1") (pintype "passive"))
    )
    (net (code "46") (name "Net-(RN2B-2)") (class "Default")
      (node (ref "RN2") (pin "7") (pinfunction "2_7") (pintype "passive"))
      (node (ref "RX") (pin "A") (pinfunction "A_A") (pintype "passive"))
    )
    (net (code "47") (name "Net-(RN2C-2)") (class "Default")
      (node (ref "RN2") (pin "6") (pinfunction "2_6") (pintype "passive"))
      (node (ref "TX") (pin "A") (pinfunction "A_A") (pintype "passive"))
    )
    (net (code "48") (name "Net-(RN4C-2)") (class "Default")
      (node (ref "ON") (pin "A") (pinfunction "A_A") (pintype "passive"))
      (node (ref "RN4") (pin "5") (pinfunction "2_5") (pintype "passive"))
      (node (ref "RN4") (pin "6") (pinfunction "2_6") (pintype "passive"))
    )
    (net (code "49") (name "Net-(X.DRV-SLEEP)") (class "Default")
      (node (ref "X.DRV") (pin "RST") (pinfunction "RST_RST") (pintype "input"))
      (node (ref "X.DRV") (pin "SLP") (pinfunction "SLEEP_SLP") (pintype "input"))
    )
    (net (code "50") (name "Net-(Y.DRV-SLEEP)") (class "Default")
      (node (ref "Y.DRV") (pin "RST") (pinfunction "RST_RST") (pintype "input"))
      (node (ref "Y.DRV") (pin "SLP") (pinfunction "SLEEP_SLP") (pintype "input"))
    )
    (net (code "51") (name "Net-(Z.DRV-SLEEP)") (class "Default")
      (node (ref "Z.DRV") (pin "RST") (pinfunction "RST_RST") (pintype "input"))
      (node (ref "Z.DRV") (pin "SLP") (pinfunction "SLEEP_SLP") (pintype "input"))
    )
    (net (code "52") (name "PB4") (class "Default")
      (node (ref "JP2") (pin "1") (pinfunction "1_1") (pintype "passive"))
      (node (ref "U3") (pin "18") (pinfunction "(T1/PCINT4)PB4_18") (pintype "bidirectional"))
    )
    (net (code "53") (name "PB5") (class "Default")
      (node (ref "JP2") (pin "3") (pinfunction "3_3") (pintype "passive"))
      (node (ref "U3") (pin "19") (pinfunction "(PCINT5)PB5_19") (pintype "bidirectional"))
    )
    (net (code "54") (name "PB6") (class "Default")
      (node (ref "JP2") (pin "2") (pinfunction "2_2") (pintype "passive"))
      (node (ref "U3") (pin "20") (pinfunction "(PCINT6)PB6_20") (pintype "bidirectional"))
    )
    (net (code "55") (name "PB7") (class "Default")
      (node (ref "JP2") (pin "4") (pinfunction "4_4") (pintype "passive"))
      (node (ref "U3") (pin "21") (pinfunction "(PCINT7/OC0A/OC1C)PB7_21") (pintype "bidirectional"))
    )
    (net (code "56") (name "PWRIN") (class "Default")
      (node (ref "D1") (pin "A") (pinfunction "A_A") (pintype "passive"))
      (node (ref "X1") (pin "2") (pinfunction "2_2") (pintype "power_in"))
    )
    (net (code "57") (name "RD+") (class "Default")
      (node (ref "RN3") (pin "4") (pinfunction "1_4") (pintype "passive"))
      (node (ref "U3") (pin "29") (pinfunction "D+_29") (pintype "bidirectional"))
    )
    (net (code "58") (name "RD-") (class "Default")
      (node (ref "RN3") (pin "1") (pinfunction "1_1") (pintype "passive"))
      (node (ref "U3") (pin "30") (pinfunction "D-_30") (pintype "bidirectional"))
    )
    (net (code "59") (name "RESET") (class "Default")
      (node (ref "C5") (pin "2") (pinfunction "2_2") (pintype "passive"))
      (node (ref "D2") (pin "A") (pinfunction "A_A") (pintype "passive"))
      (node (ref "E.STP") (pin "1") (pinfunction "1_1") (pintype "passive"))
      (node (ref "ICSP") (pin "5") (pinfunction "5_5") (pintype "passive"))
      (node (ref "POWER") (pin "3") (pinfunction "3_3") (pintype "passive"))
      (node (ref "RESET") (pin "3") (pinfunction "3_3") (pintype "passive"))
      (node (ref "RESET") (pin "4") (pinfunction "4_4") (pintype "passive"))
      (node (ref "RESET-EN") (pin "1") (pinfunction "1_1") (pintype "passive"))
      (node (ref "RESET-EN") (pin "2") (pinfunction "2_2") (pintype "passive"))
      (node (ref "RN1") (pin "4") (pinfunction "1_4") (pintype "passive"))
      (node (ref "ZU4") (pin "1") (pinfunction "RESET_1") (pintype "input"))
    )
    (net (code "60") (name "RESET2") (class "Default")
      (node (ref "D3") (pin "A") (pinfunction "A_A") (pintype "passive"))
      (node (ref "ICSP1") (pin "5") (pinfunction "5_5") (pintype "passive"))
      (node (ref "RN1") (pin "6") (pinfunction "2_6") (pintype "passive"))
      (node (ref "U3") (pin "24") (pinfunction "RESET(PC1/DW)_24") (pintype "input"))
    )
    (net (code "61") (name "RXLED") (class "Default")
      (node (ref "RX") (pin "C") (pinfunction "C_C") (pintype "passive"))
      (node (ref "U3") (pin "10") (pinfunction "(INT5/AIN3)PD4_10") (pintype "bidirectional"))
    )
    (net (code "62") (name "SCK") (class "Default")
      (node (ref "ICSP") (pin "3") (pinfunction "3_3") (pintype "passive"))
      (node (ref "IOH") (pin "6") (pinfunction "6_6") (pintype "passive"))
      (node (ref "SP.DR") (pin "1") (pinfunction "1_1") (pintype "passive"))
      (node (ref "U5") (pin "5") (pinfunction "+IN_5") (pintype "input"))
      (node (ref "ZU4") (pin "19") (pinfunction "(SCK)PB5_19") (pintype "bidirectional"))
    )
    (net (code "63") (name "SCK2") (class "Default")
      (node (ref "ICSP1") (pin "3") (pinfunction "3_3") (pintype "passive"))
      (node (ref "U3") (pin "15") (pinfunction "(SCLK/PCINT1)PB1_15") (pintype "bidirectional"))
    )
    (net (code "64") (name "SS") (class "Default")
      (node (ref "C16") (pin "1") (pinfunction "1_1") (pintype "passive"))
      (node (ref "IOH") (pin "3") (pinfunction "3_3") (pintype "passive"))
      (node (ref "RN6") (pin "7") (pinfunction "2_7") (pintype "passive"))
      (node (ref "Y+.LIM") (pin "1") (pinfunction "1_1") (pintype "passive"))
      (node (ref "Y-.LIM") (pin "1") (pinfunction "1_1") (pintype "passive"))
      (node (ref "ZU4") (pin "16") (pinfunction "(SS)PB2_16") (pintype "bidirectional"))
    )
    (net (code "65") (name "TP_VUCAP") (class "Default")
      (node (ref "C8") (pin "1") (pinfunction "1_1") (pintype "passive"))
      (node (ref "U3") (pin "27") (pinfunction "UCAP_27") (pintype "passive"))
    )
    (net (code "66") (name "TXLED") (class "Default")
      (node (ref "TX") (pin "C") (pinfunction "C_C") (pintype "passive"))
      (node (ref "U3") (pin "11") (pinfunction "(XCK/AIN4/PCINT12)PD5_11") (pintype "bidirectional"))
    )
    (net (code "67") (name "UGND") (class "Default")
      (node (ref "C8") (pin "2") (pinfunction "2_2") (pintype "passive"))
      (node (ref "GROUND") (pin "2") (pinfunction "2_2") (pintype "passive"))
      (node (ref "L1") (pin "1") (pinfunction "1_1") (pintype "passive"))
      (node (ref "U3") (pin "28") (pinfunction "UGND_28") (pintype "power_in"))
      (node (ref "X2") (pin "4") (pinfunction "4_4") (pintype "bidirectional"))
    )
    (net (code "68") (name "USBVCC") (class "Default")
      (node (ref "F1") (pin "1") (pinfunction "1_1") (pintype "passive"))
      (node (ref "T1") (pin "1") (pinfunction "D_1") (pintype "passive"))
      (node (ref "U3") (pin "31") (pinfunction "UVCC_31") (pintype "power_in"))
    )
    (net (code "69") (name "USHIELD") (class "Default")
      (node (ref "L1") (pin "2") (pinfunction "2_2") (pintype "passive"))
      (node (ref "X2") (pin "P$1") (pinfunction "P$1_P$1") (pintype "bidirectional"))
      (node (ref "X2") (pin "P$2") (pinfunction "P$2_P$2") (pintype "bidirectional"))
      (node (ref "Z1") (pin "2") (pinfunction "2_2") (pintype "passive"))
      (node (ref "Z2") (pin "2") (pinfunction "2_2") (pintype "passive"))
    )
    (net (code "70") (name "V.MOT") (class "Default")
      (node (ref "A.DRV") (pin "VMOT") (pinfunction "VMOT_VMOT") (pintype "power_in"))
      (node (ref "C10") (pin "1") (pinfunction "+_1") (pintype "passive"))
      (node (ref "C12") (pin "1") (pinfunction "+_1") (pintype "passive"))
      (node (ref "C13") (pin "1") (pinfunction "+_1") (pintype "passive"))
      (node (ref "C14") (pin "1") (pinfunction "+_1") (pintype "passive"))
      (node (ref "MOT.PWR") (pin "1") (pinfunction "1_1") (pintype "passive"))
      (node (ref "X.DRV") (pin "VMOT") (pinfunction "VMOT_VMOT") (pintype "power_in"))
      (node (ref "Y.DRV") (pin "VMOT") (pinfunction "VMOT_VMOT") (pintype "power_in"))
      (node (ref "Z.DRV") (pin "VMOT") (pinfunction "VMOT_VMOT") (pintype "power_in"))
    )
    (net (code "71") (name "VIN") (class "Default")
      (node (ref "D1") (pin "C") (pinfunction "C_C") (pintype "passive"))
      (node (ref "PC1") (pin "+") (pinfunction "+_+") (pintype "passive"))
      (node (ref "POWER") (pin "8") (pinfunction "8_8") (pintype "passive"))
      (node (ref "RN1") (pin "8") (pinfunction "2_8") (pintype "passive"))
      (node (ref "U1") (pin "3") (pinfunction "IN_3") (pintype "input"))
    )
    (net (code "72") (name "X.A1") (class "Default")
      (node (ref "X.DRV") (pin "1A") (pinfunction "1A_1A") (pintype "output"))
      (node (ref "X.MOT") (pin "3") (pinfunction "3_3") (pintype "passive"))
    )
    (net (code "73") (name "X.A2") (class "Default")
      (node (ref "X.DRV") (pin "1B") (pinfunction "1B_1B") (pintype "output"))
      (node (ref "X.MOT") (pin "4") (pinfunction "4_4") (pintype "passive"))
    )
    (net (code "74") (name "X.B1") (class "Default")
      (node (ref "X.DRV") (pin "2A") (pinfunction "2A_2A") (pintype "output"))
      (node (ref "X.MOT") (pin "2") (pinfunction "2_2") (pintype "passive"))
    )
    (net (code "75") (name "X.B2") (class "Default")
      (node (ref "X.DRV") (pin "2B") (pinfunction "2B_2B") (pintype "output"))
      (node (ref "X.MOT") (pin "1") (pinfunction "1_1") (pintype "passive"))
    )
    (net (code "76") (name "XM0") (class "Default")
      (node (ref "X.DRV") (pin "MS1") (pinfunction "MS1_MS1") (pintype "input"))
      (node (ref "X.M0") (pin "1") (pinfunction "1_1") (pintype "passive"))
    )
    (net (code "77") (name "XM1") (class "Default")
      (node (ref "X.DRV") (pin "MS2") (pinfunction "MS2_MS2") (pintype "input"))
      (node (ref "X.M1") (pin "1") (pinfunction "1_1") (pintype "passive"))
    )
    (net (code "78") (name "XM2") (class "Default")
      (node (ref "X.DRV") (pin "MS3") (pinfunction "MS3_MS3") (pintype "input"))
      (node (ref "X.M2") (pin "1") (pinfunction "1_1") (pintype "passive"))
    )
    (net (code "79") (name "XT1") (class "Default")
      (node (ref "C9") (pin "1") (pinfunction "1_1") (pintype "passive"))
      (node (ref "R1") (pin "1") (pinfunction "1_1") (pintype "passive"))
      (node (ref "U3") (pin "1") (pinfunction "XTAL1_1") (pintype "bidirectional"))
      (node (ref "Y1") (pin "2") (pinfunction "2_2") (pintype "passive"))
    )
    (net (code "80") (name "XT2") (class "Default")
      (node (ref "C11") (pin "1") (pinfunction "1_1") (pintype "passive"))
      (node (ref "R1") (pin "2") (pinfunction "2_2") (pintype "passive"))
      (node (ref "U3") (pin "2") (pinfunction "XTAL2(PC0)_2") (pintype "bidirectional"))
      (node (ref "Y1") (pin "1") (pinfunction "1_1") (pintype "passive"))
    )
    (net (code "81") (name "XTAL1") (class "Default")
      (node (ref "R2") (pin "1") (pinfunction "1_1") (pintype "passive"))
      (node (ref "Y2") (pin "3") (pinfunction "3_3") (pintype "passive"))
      (node (ref "ZU4") (pin "9") (pinfunction "XTAL1_9") (pintype "bidirectional"))
    )
    (net (code "82") (name "XTAL2") (class "Default")
      (node (ref "R2") (pin "2") (pinfunction "2_2") (pintype "passive"))
      (node (ref "Y2") (pin "1") (pinfunction "1_1") (pintype "passive"))
      (node (ref "ZU4") (pin "10") (pinfunction "XTAL2_10") (pintype "bidirectional"))
    )
    (net (code "83") (name "XUSB") (class "Default")
      (node (ref "F1") (pin "2") (pinfunction "2_2") (pintype "passive"))
      (node (ref "X2") (pin "1") (pinfunction "1_1") (pintype "bidirectional"))
    )
    (net (code "84") (name "Y.A1") (class "Default")
      (node (ref "Y.DRV") (pin "1A") (pinfunction "1A_1A") (pintype "output"))
      (node (ref "Y.MOT") (pin "3") (pinfunction "3_3") (pintype "passive"))
    )
    (net (code "85") (name "Y.A2") (class "Default")
      (node (ref "Y.DRV") (pin "1B") (pinfunction "1B_1B") (pintype "output"))
      (node (ref "Y.MOT") (pin "4") (pinfunction "4_4") (pintype "passive"))
    )
    (net (code "86") (name "Y.B1") (class "Default")
      (node (ref "Y.DRV") (pin "2A") (pinfunction "2A_2A") (pintype "output"))
      (node (ref "Y.MOT") (pin "2") (pinfunction "2_2") (pintype "passive"))
    )
    (net (code "87") (name "Y.B2") (class "Default")
      (node (ref "Y.DRV") (pin "2B") (pinfunction "2B_2B") (pintype "output"))
      (node (ref "Y.MOT") (pin "1") (pinfunction "1_1") (pintype "passive"))
    )
    (net (code "88") (name "YM0") (class "Default")
      (node (ref "Y.DRV") (pin "MS1") (pinfunction "MS1_MS1") (pintype "input"))
      (node (ref "Y.M0") (pin "1") (pinfunction "1_1") (pintype "passive"))
    )
    (net (code "89") (name "YM1") (class "Default")
      (node (ref "Y.DRV") (pin "MS2") (pinfunction "MS2_MS2") (pintype "input"))
      (node (ref "Y.M1") (pin "1") (pinfunction "1_1") (pintype "passive"))
    )
    (net (code "90") (name "YM2") (class "Default")
      (node (ref "Y.DRV") (pin "MS3") (pinfunction "MS3_MS3") (pintype "input"))
      (node (ref "Y.M2") (pin "1") (pinfunction "1_1") (pintype "passive"))
    )
    (net (code "91") (name "Z.A1") (class "Default")
      (node (ref "Z.DRV") (pin "1A") (pinfunction "1A_1A") (pintype "output"))
      (node (ref "Z.MOT") (pin "3") (pinfunction "3_3") (pintype "passive"))
    )
    (net (code "92") (name "Z.A2") (class "Default")
      (node (ref "Z.DRV") (pin "1B") (pinfunction "1B_1B") (pintype "output"))
      (node (ref "Z.MOT") (pin "4") (pinfunction "4_4") (pintype "passive"))
    )
    (net (code "93") (name "Z.B1") (class "Default")
      (node (ref "Z.DRV") (pin "2A") (pinfunction "2A_2A") (pintype "output"))
      (node (ref "Z.MOT") (pin "2") (pinfunction "2_2") (pintype "passive"))
    )
    (net (code "94") (name "Z.B2") (class "Default")
      (node (ref "Z.DRV") (pin "2B") (pinfunction "2B_2B") (pintype "output"))
      (node (ref "Z.MOT") (pin "1") (pinfunction "1_1") (pintype "passive"))
    )
    (net (code "95") (name "ZM0") (class "Default")
      (node (ref "Z.DRV") (pin "MS1") (pinfunction "MS1_MS1") (pintype "input"))
      (node (ref "Z.M0") (pin "1") (pinfunction "1_1") (pintype "passive"))
    )
    (net (code "96") (name "ZM1") (class "Default")
      (node (ref "Z.DRV") (pin "MS2") (pinfunction "MS2_MS2") (pintype "input"))
      (node (ref "Z.M1") (pin "1") (pinfunction "1_1") (pintype "passive"))
    )
    (net (code "97") (name "ZM2") (class "Default")
      (node (ref "Z.DRV") (pin "MS3") (pinfunction "MS3_MS3") (pintype "input"))
      (node (ref "Z.M2") (pin "1") (pinfunction "1_1") (pintype "passive"))
    )
    (net (code "98") (name "unconnected-(POWER-Pad1)") (class "Default")
      (node (ref "POWER") (pin "1") (pinfunction "1_1") (pintype "passive"))
    )
    (net (code "99") (name "unconnected-(RN3B-1-Pad2)") (class "Default")
      (node (ref "RN3") (pin "2") (pinfunction "1_2") (pintype "passive"))
    )
    (net (code "100") (name "unconnected-(RN3B-2-Pad7)") (class "Default")
      (node (ref "RN3") (pin "7") (pinfunction "2_7") (pintype "passive"))
    )
    (net (code "101") (name "unconnected-(RN3C-1-Pad3)") (class "Default")
      (node (ref "RN3") (pin "3") (pinfunction "1_3") (pintype "passive"))
    )
    (net (code "102") (name "unconnected-(RN3C-2-Pad6)") (class "Default")
      (node (ref "RN3") (pin "6") (pinfunction "2_6") (pintype "passive"))
    )
    (net (code "103") (name "unconnected-(U2-NC{slash}FB-Pad4)") (class "Default")
      (node (ref "U2") (pin "4") (pinfunction "NC/FB_4") (pintype "passive"))
    )
    (net (code "104") (name "unconnected-(U3-(AIN0{slash}INT1)PD1-Pad7)") (class "Default")
      (node (ref "U3") (pin "7") (pinfunction "(AIN0/INT1)PD1_7") (pintype "bidirectional"))
    )
    (net (code "105") (name "unconnected-(U3-(AIN2{slash}PCINT11)PC2-Pad5)") (class "Default")
      (node (ref "U3") (pin "5") (pinfunction "(AIN2/PCINT11)PC2_5") (pintype "bidirectional"))
    )
    (net (code "106") (name "unconnected-(U3-(INT4{slash}ICP1{slash}CLK0)PC7-Pad22)") (class "Default")
      (node (ref "U3") (pin "22") (pinfunction "(INT4/ICP1/CLK0)PC7_22") (pintype "bidirectional"))
    )
    (net (code "107") (name "unconnected-(U3-(OC0B{slash}INT0)PD0-Pad6)") (class "Default")
      (node (ref "U3") (pin "6") (pinfunction "(OC0B/INT0)PD0_6") (pintype "bidirectional"))
    )
    (net (code "108") (name "unconnected-(U3-(OC1A{slash}PCINT8)PC6-Pad23)") (class "Default")
      (node (ref "U3") (pin "23") (pinfunction "(OC1A/PCINT8)PC6_23") (pintype "bidirectional"))
    )
    (net (code "109") (name "unconnected-(U3-(PCINT9{slash}OC1B)PC5-Pad25)") (class "Default")
      (node (ref "U3") (pin "25") (pinfunction "(PCINT9/OC1B)PC5_25") (pintype "bidirectional"))
    )
    (net (code "110") (name "unconnected-(U3-(PCINT10)PC4-Pad26)") (class "Default")
      (node (ref "U3") (pin "26") (pinfunction "(PCINT10)PC4_26") (pintype "bidirectional"))
    )
    (net (code "111") (name "unconnected-(U3-(RTS{slash}AIN5{slash}INT6)PD6-Pad12)") (class "Default")
      (node (ref "U3") (pin "12") (pinfunction "(RTS/AIN5/INT6)PD6_12") (pintype "bidirectional"))
    )
    (net (code "112") (name "unconnected-(U3-(SS{slash}PCINT0)PB0-Pad14)") (class "Default")
      (node (ref "U3") (pin "14") (pinfunction "(SS/PCINT0)PB0_14") (pintype "bidirectional"))
    )
  )
)
